# AST1035.net
KiCad netlist of a schematic drawn in EAGLE
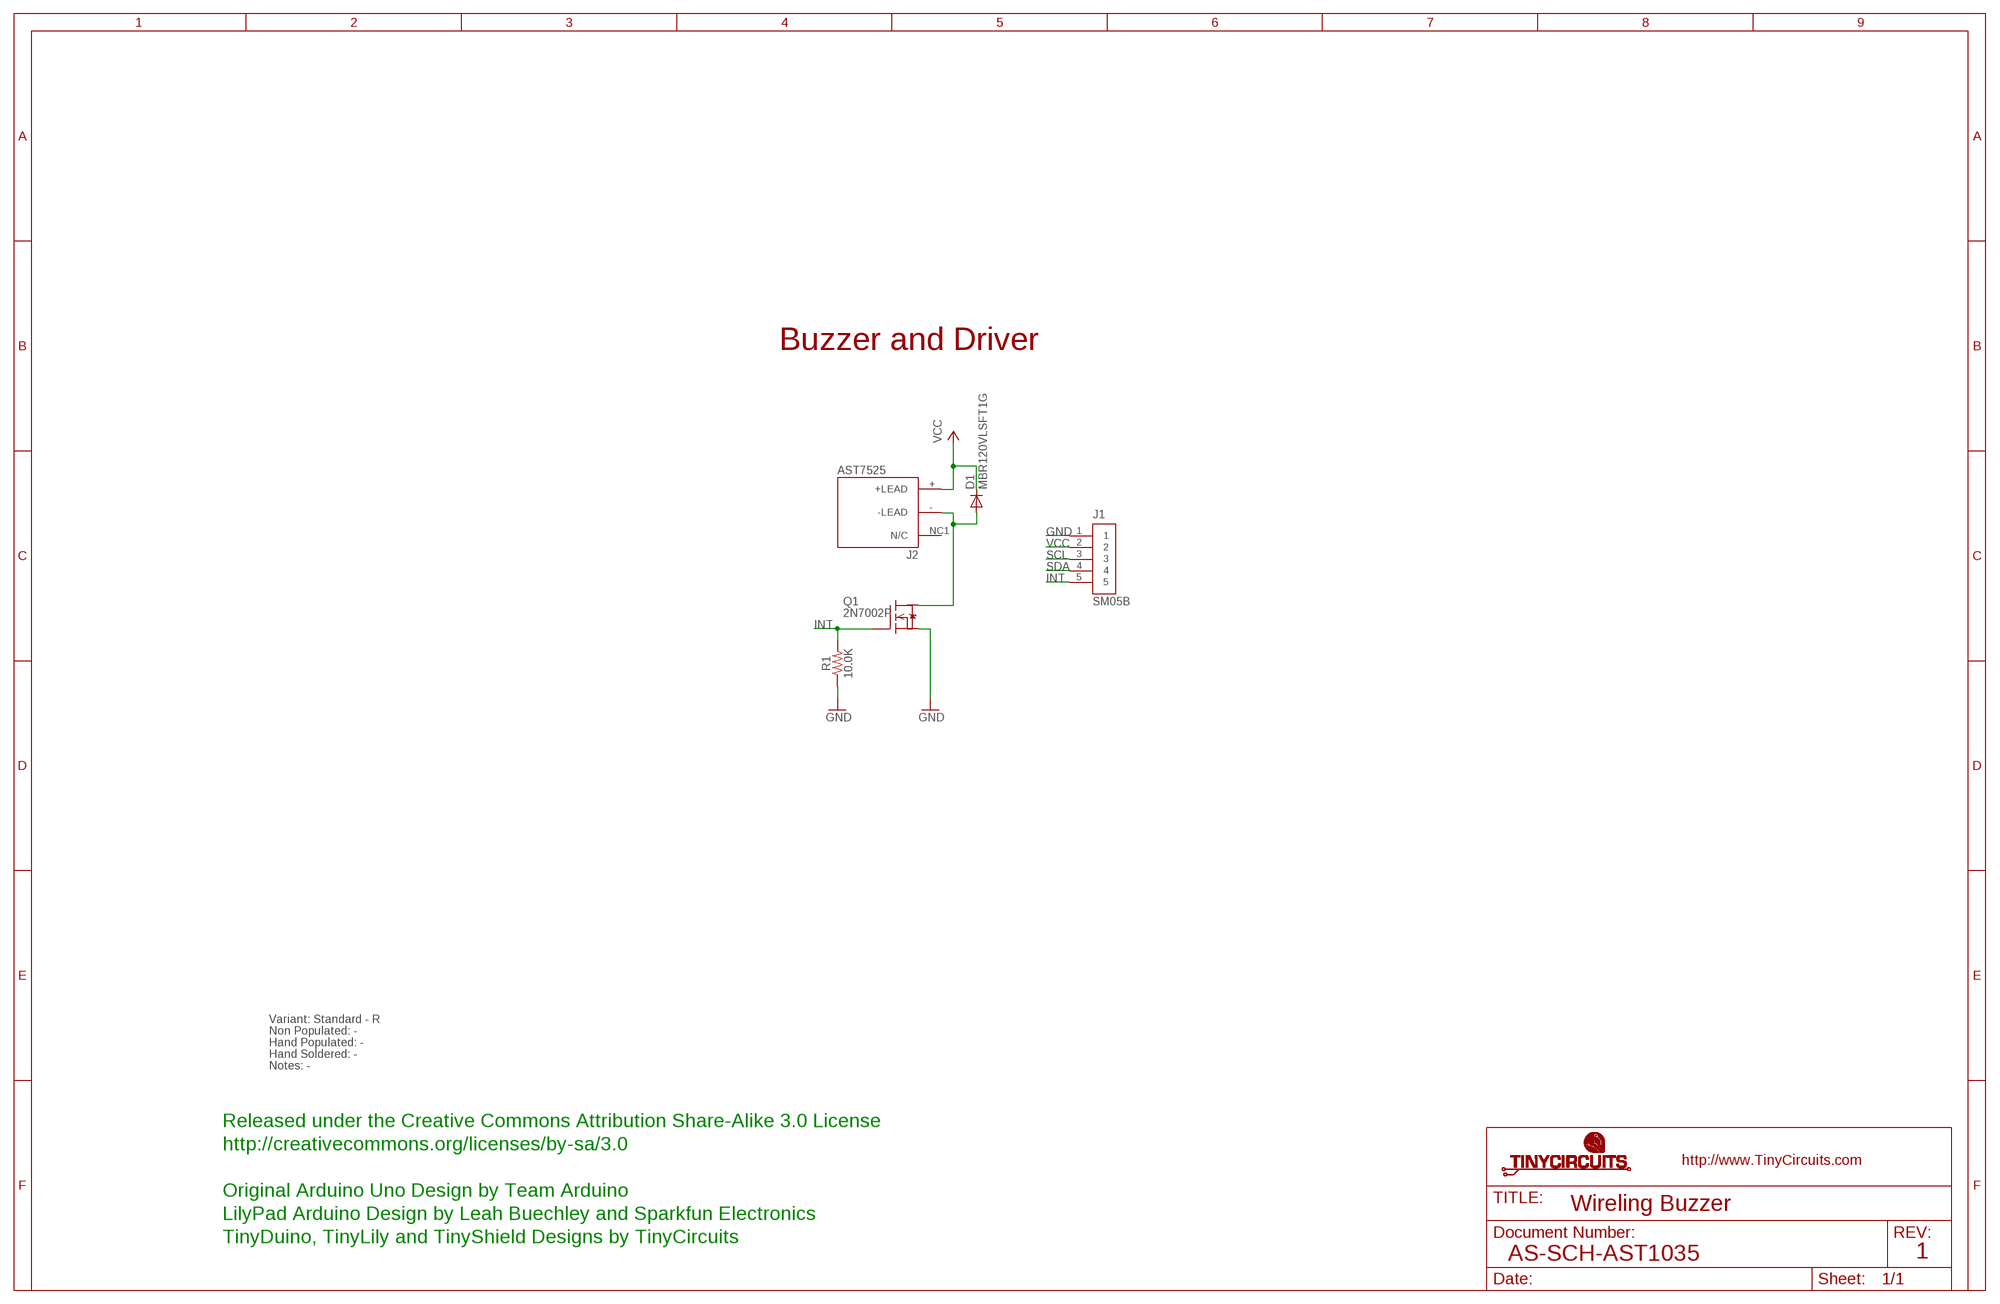
[diagram p0: schematic, sheet 1]

(export (version "E")
  (design (tool "Eeschema 10.0.6"))
  (components
    (comp (ref "D1")
      (value "MBR120VLSFT1G")
      (footprint "eagle-import:SOD-123FL")
      (fields (field (name "PARTNO") "AS-ITM-00111"))
      (libsource (lib "eagle-import") (part "AS-ITM-00111"))
    )
    (comp (ref "J1")
      (value "SM05B")
      (footprint "eagle-import:JST_SH_5X1_EDGE")
      (fields (field (name "PARTNO") "AS-ITM-00340"))
      (libsource (lib "eagle-import") (part "AS-ITM-00340EDGE"))
    )
    (comp (ref "J2")
      (value "AST7525")
      (footprint "eagle-import:AST7525")
      (fields (field (name "PARTNO") "AS-ITM-00390"))
      (libsource (lib "eagle-import") (part "AS-ITM-00390"))
    )
    (comp (ref "Q1")
      (value "2N7002P")
      (footprint "eagle-import:SOT23A")
      (fields (field (name "PARTNO") "AS-ITM-00007"))
      (libsource (lib "eagle-import") (part "AS-ITM-00007C"))
    )
    (comp (ref "R1")
      (value "10.0K")
      (footprint "eagle-import:0402")
      (fields (field (name "PARTNO") "AS-ITM-00032"))
      (libsource (lib "eagle-import") (part "AS-ITM-00032"))
    )
  )
  (nets
    (net (code "1") (name "/INT") (class "Default")
      (node (ref "J1") (pin "5") (pinfunction "5_5") (pintype "bidirectional"))
      (node (ref "Q1") (pin "B") (pinfunction "G_B") (pintype "passive"))
      (node (ref "R1") (pin "2") (pinfunction "2_2") (pintype "passive"))
    )
    (net (code "2") (name "/SCL") (class "Default")
      (node (ref "J1") (pin "3") (pinfunction "3_3") (pintype "bidirectional"))
    )
    (net (code "3") (name "/SDA") (class "Default")
      (node (ref "J1") (pin "4") (pinfunction "4_4") (pintype "bidirectional"))
    )
    (net (code "4") (name "GND") (class "Default")
      (node (ref "J1") (pin "1") (pinfunction "1_1") (pintype "bidirectional"))
      (node (ref "Q1") (pin "E") (pinfunction "S_E") (pintype "passive"))
      (node (ref "R1") (pin "1") (pinfunction "1_1") (pintype "passive"))
    )
    (net (code "5") (name "Net-(J2--LEAD)") (class "Default")
      (node (ref "D1") (pin "A") (pinfunction "A_A") (pintype "passive"))
      (node (ref "J2") (pin "-") (pinfunction "-LEAD_-") (pintype "bidirectional"))
      (node (ref "Q1") (pin "C") (pinfunction "D_C") (pintype "passive"))
    )
    (net (code "6") (name "VCC") (class "Default")
      (node (ref "D1") (pin "C") (pinfunction "C_C") (pintype "passive"))
      (node (ref "J1") (pin "2") (pinfunction "2_2") (pintype "bidirectional"))
      (node (ref "J2") (pin "+") (pinfunction "+LEAD_+") (pintype "bidirectional"))
    )
    (net (code "7") (name "unconnected-(J2-N{slash}C-PadNC1)") (class "Default")
      (node (ref "J2") (pin "NC1") (pinfunction "N/C_NC1") (pintype "bidirectional"))
    )
  )
)
